# auto_week_3.net
KiCad netlist of a schematic drawn in EAGLE
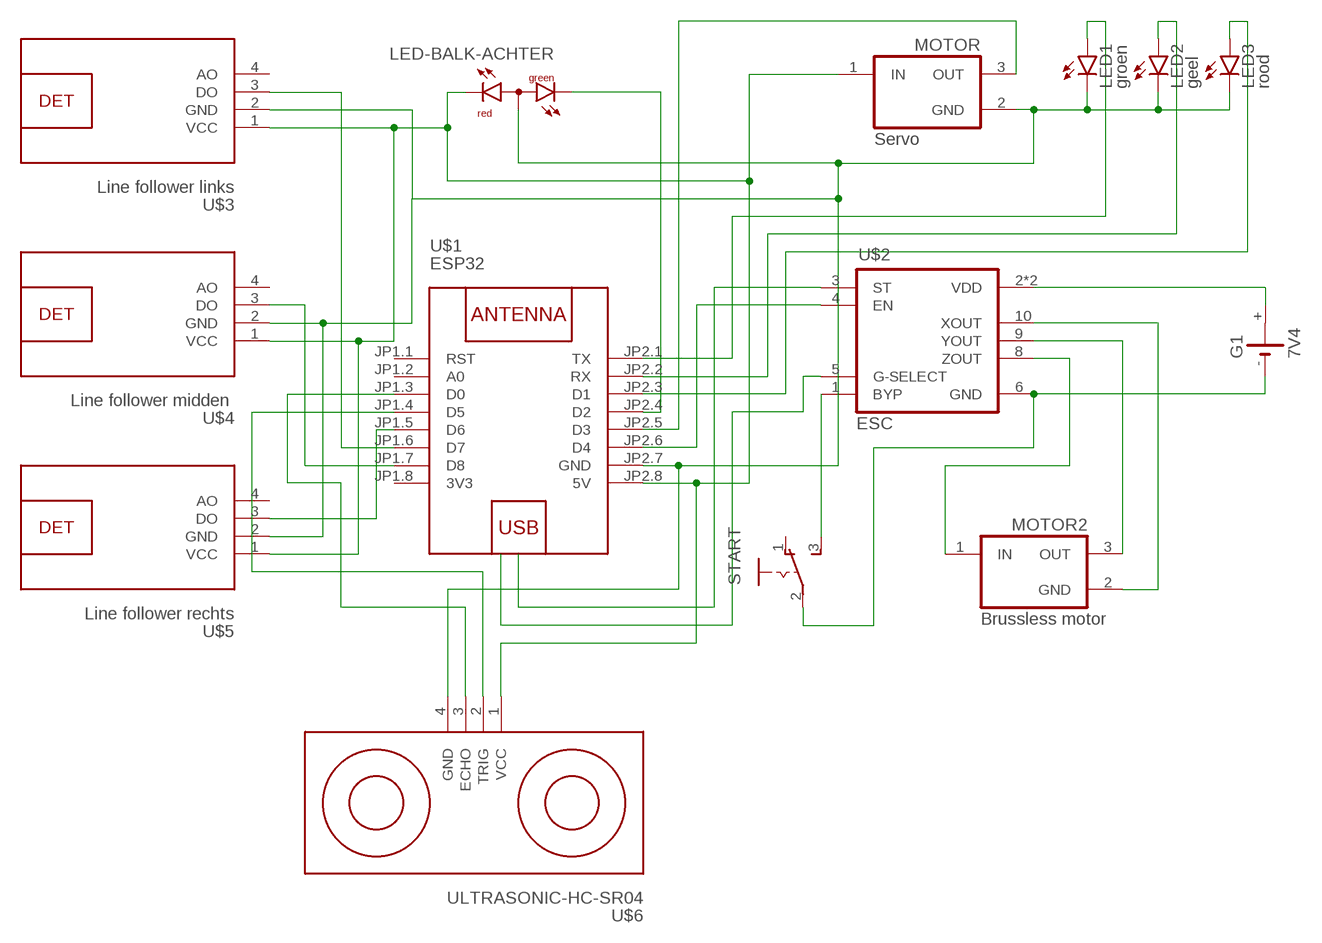
[diagram p0: schematic, sheet 1]

(export (version "E")
  (design (tool "Eeschema 10.0.6"))
  (components
    (comp (ref "G1")
      (value "7V4")
      (footprint "eagle-import:1V60R")
      (libsource (lib "eagle-import") (part "1V60R"))
    )
    (comp (ref "LED-BALK-ACHTER")
      (value "DUOLED-RG-A")
      (footprint "eagle-import:DUOLED-A-5MM")
      (libsource (lib "eagle-import") (part "DUOLED-RG-A"))
    )
    (comp (ref "LED1")
      (value "groen")
      (footprint "eagle-import:P47F-BOTTOM")
      (libsource (lib "eagle-import") (part "P4-BOTTOMLA"))
    )
    (comp (ref "LED2")
      (value "geel")
      (footprint "eagle-import:P47F-BOTTOM")
      (libsource (lib "eagle-import") (part "P4-BOTTOMLA"))
    )
    (comp (ref "LED3")
      (value "rood")
      (footprint "eagle-import:P47F-BOTTOM")
      (libsource (lib "eagle-import") (part "P4-BOTTOMLA"))
    )
    (comp (ref "MOTOR")
      (value "Servo")
      (footprint "eagle-import:TO220-S")
      (libsource (lib "eagle-import") (part "MIC29300-3.3BT"))
    )
    (comp (ref "MOTOR2")
      (value "Brussless motor")
      (footprint "eagle-import:TO220-S")
      (libsource (lib "eagle-import") (part "MIC29300-3.3BT"))
    )
    (comp (ref "START")
      (value "255SB")
      (footprint "eagle-import:255SB")
      (libsource (lib "eagle-import") (part "255SB"))
    )
    (comp (ref "U$1")
      (value "ESP32")
      (footprint "eagle-import:WEMOS-D1-MINI")
      (libsource (lib "eagle-import") (part "WEMOS-D1-MINI"))
    )
    (comp (ref "U$2")
      (value "ESC")
      (footprint "eagle-import:QFN12-3X3")
      (libsource (lib "eagle-import") (part "FXLN83XXQ"))
    )
    (comp (ref "U$3")
      (value "Line follower links")
      (footprint "eagle-import:FLAME-DETECTOR")
      (libsource (lib "eagle-import") (part "FLAME-DETECTOR"))
    )
    (comp (ref "U$4")
      (value "Line follower midden")
      (footprint "eagle-import:FLAME-DETECTOR")
      (libsource (lib "eagle-import") (part "FLAME-DETECTOR"))
    )
    (comp (ref "U$5")
      (value "Line follower rechts")
      (footprint "eagle-import:FLAME-DETECTOR")
      (libsource (lib "eagle-import") (part "FLAME-DETECTOR"))
    )
    (comp (ref "U$6")
      (value "ULTRASONIC-HC-SR04")
      (footprint "eagle-import:ULTRASONIC-HC-SR04")
      (libsource (lib "eagle-import") (part "ULTRASONIC-HC-SR04"))
    )
  )
  (nets
    (net (code "1") (name "/3V3") (class "Default")
      (node (ref "U$1") (pin "JP1.8") (pinfunction "3V3_JP1.8") (pintype "power_in"))
    )
    (net (code "2") (name "Net-(G1-Pad+)") (class "Default")
      (node (ref "G1") (pin "+") (pinfunction "+_+") (pintype "passive"))
      (node (ref "U$2") (pin "2") (pinfunction "VDD_2") (pintype "power_in"))
      (node (ref "U$2") (pin "7") (pinfunction "VDD_7") (pintype "power_in"))
    )
    (net (code "3") (name "Net-(LED-BALK-ACHTER-CG)") (class "Default")
      (node (ref "LED-BALK-ACHTER") (pin "CX") (pinfunction "CG_CX") (pintype "passive"))
      (node (ref "U$1") (pin "JP2.4") (pinfunction "D2_JP2.4") (pintype "bidirectional"))
    )
    (net (code "4") (name "Net-(MOTOR-GND)") (class "Default")
      (node (ref "LED-BALK-ACHTER") (pin "A") (pinfunction "A_A") (pintype "passive"))
      (node (ref "LED1") (pin "C") (pinfunction "C_C") (pintype "passive"))
      (node (ref "LED2") (pin "C") (pinfunction "C_C") (pintype "passive"))
      (node (ref "LED3") (pin "C") (pinfunction "C_C") (pintype "passive"))
      (node (ref "MOTOR") (pin "2") (pinfunction "GND_2") (pintype "power_in"))
      (node (ref "U$1") (pin "JP2.7") (pinfunction "GND_JP2.7") (pintype "power_in"))
      (node (ref "U$3") (pin "2") (pinfunction "GND_2") (pintype "power_in"))
      (node (ref "U$4") (pin "2") (pinfunction "GND_2") (pintype "power_in"))
      (node (ref "U$5") (pin "2") (pinfunction "GND_2") (pintype "power_in"))
      (node (ref "U$6") (pin "4") (pinfunction "GND_4") (pintype "power_in"))
    )
    (net (code "5") (name "Net-(MOTOR-IN)") (class "Default")
      (node (ref "LED-BALK-ACHTER") (pin "CR") (pinfunction "CR_CR") (pintype "passive"))
      (node (ref "MOTOR") (pin "1") (pinfunction "IN_1") (pintype "passive"))
      (node (ref "U$1") (pin "JP2.8") (pinfunction "5V_JP2.8") (pintype "power_in"))
      (node (ref "U$3") (pin "1") (pinfunction "VCC_1") (pintype "power_in"))
      (node (ref "U$4") (pin "1") (pinfunction "VCC_1") (pintype "power_in"))
      (node (ref "U$5") (pin "1") (pinfunction "VCC_1") (pintype "power_in"))
      (node (ref "U$6") (pin "1") (pinfunction "VCC_1") (pintype "power_in"))
    )
    (net (code "6") (name "Net-(MOTOR-OUT)") (class "Default")
      (node (ref "MOTOR") (pin "3") (pinfunction "OUT_3") (pintype "passive"))
      (node (ref "U$1") (pin "JP2.5") (pinfunction "D3_JP2.5") (pintype "bidirectional"))
    )
    (net (code "7") (name "Net-(MOTOR2-GND)") (class "Default")
      (node (ref "MOTOR2") (pin "2") (pinfunction "GND_2") (pintype "power_in"))
      (node (ref "U$2") (pin "10") (pinfunction "XOUT_10") (pintype "output"))
    )
    (net (code "8") (name "Net-(MOTOR2-IN)") (class "Default")
      (node (ref "MOTOR2") (pin "1") (pinfunction "IN_1") (pintype "passive"))
      (node (ref "U$2") (pin "8") (pinfunction "ZOUT_8") (pintype "output"))
    )
    (net (code "9") (name "Net-(MOTOR2-OUT)") (class "Default")
      (node (ref "MOTOR2") (pin "3") (pinfunction "OUT_3") (pintype "passive"))
      (node (ref "U$2") (pin "9") (pinfunction "YOUT_9") (pintype "output"))
    )
    (net (code "10") (name "Net-(START-P)") (class "Default")
      (node (ref "G1") (pin "-") (pinfunction "-_-") (pintype "passive"))
      (node (ref "START") (pin "2") (pinfunction "P_2") (pintype "passive"))
      (node (ref "U$2") (pin "6") (pinfunction "GND_6") (pintype "power_in"))
    )
    (net (code "11") (name "Net-(START-S)") (class "Default")
      (node (ref "START") (pin "3") (pinfunction "S_3") (pintype "passive"))
      (node (ref "U$2") (pin "1") (pinfunction "BYP_1") (pintype "bidirectional"))
    )
    (net (code "12") (name "Net-(U$1-D0)") (class "Default")
      (node (ref "U$1") (pin "JP1.3") (pinfunction "D0_JP1.3") (pintype "bidirectional"))
      (node (ref "U$6") (pin "3") (pinfunction "ECHO_3") (pintype "output"))
    )
    (net (code "13") (name "Net-(U$1-D1)") (class "Default")
      (node (ref "LED3") (pin "A") (pinfunction "A_A") (pintype "passive"))
      (node (ref "U$1") (pin "JP2.3") (pinfunction "D1_JP2.3") (pintype "bidirectional"))
    )
    (net (code "14") (name "Net-(U$1-D4)") (class "Default")
      (node (ref "U$1") (pin "JP2.6") (pinfunction "D4_JP2.6") (pintype "bidirectional"))
      (node (ref "U$2") (pin "4") (pinfunction "EN_4") (pintype "bidirectional"))
    )
    (net (code "15") (name "Net-(U$1-D5)") (class "Default")
      (node (ref "U$1") (pin "JP1.4") (pinfunction "D5_JP1.4") (pintype "bidirectional"))
      (node (ref "U$6") (pin "2") (pinfunction "TRIG_2") (pintype "input"))
    )
    (net (code "16") (name "Net-(U$1-D6)") (class "Default")
      (node (ref "U$1") (pin "JP1.5") (pinfunction "D6_JP1.5") (pintype "bidirectional"))
      (node (ref "U$5") (pin "3") (pinfunction "DO_3") (pintype "bidirectional"))
    )
    (net (code "17") (name "Net-(U$1-D7)") (class "Default")
      (node (ref "U$1") (pin "JP1.6") (pinfunction "D7_JP1.6") (pintype "bidirectional"))
      (node (ref "U$3") (pin "3") (pinfunction "DO_3") (pintype "bidirectional"))
    )
    (net (code "18") (name "Net-(U$1-D8)") (class "Default")
      (node (ref "U$1") (pin "JP1.7") (pinfunction "D8_JP1.7") (pintype "bidirectional"))
      (node (ref "U$4") (pin "3") (pinfunction "DO_3") (pintype "bidirectional"))
    )
    (net (code "19") (name "Net-(U$1-RX)") (class "Default")
      (node (ref "LED2") (pin "A") (pinfunction "A_A") (pintype "passive"))
      (node (ref "U$1") (pin "JP2.2") (pinfunction "RX_JP2.2") (pintype "bidirectional"))
    )
    (net (code "20") (name "Net-(U$1-TX)") (class "Default")
      (node (ref "LED1") (pin "A") (pinfunction "A_A") (pintype "passive"))
      (node (ref "U$1") (pin "JP2.1") (pinfunction "TX_JP2.1") (pintype "bidirectional"))
    )
    (net (code "21") (name "unconnected-(G1-+-Pad+@1)") (class "Default")
      (node (ref "G1") (pin "+@1") (pinfunction "+_+@1") (pintype "passive"))
    )
    (net (code "22") (name "unconnected-(START-O-Pad1)") (class "Default")
      (node (ref "START") (pin "1") (pinfunction "O_1") (pintype "passive"))
    )
    (net (code "23") (name "unconnected-(U$1-A0-PadJP1.2)") (class "Default")
      (node (ref "U$1") (pin "JP1.2") (pinfunction "A0_JP1.2") (pintype "bidirectional"))
    )
    (net (code "24") (name "unconnected-(U$1-RST-PadJP1.1)") (class "Default")
      (node (ref "U$1") (pin "JP1.1") (pinfunction "RST_JP1.1") (pintype "bidirectional"))
    )
    (net (code "25") (name "unconnected-(U$2-G-SELECT-Pad5)") (class "Default")
      (node (ref "U$2") (pin "5") (pinfunction "G-SELECT_5") (pintype "bidirectional"))
    )
    (net (code "26") (name "unconnected-(U$2-ST-Pad3)") (class "Default")
      (node (ref "U$2") (pin "3") (pinfunction "ST_3") (pintype "bidirectional"))
    )
    (net (code "27") (name "unconnected-(U$3-AO-Pad4)") (class "Default")
      (node (ref "U$3") (pin "4") (pinfunction "AO_4") (pintype "bidirectional"))
    )
    (net (code "28") (name "unconnected-(U$4-AO-Pad4)") (class "Default")
      (node (ref "U$4") (pin "4") (pinfunction "AO_4") (pintype "bidirectional"))
    )
    (net (code "29") (name "unconnected-(U$5-AO-Pad4)") (class "Default")
      (node (ref "U$5") (pin "4") (pinfunction "AO_4") (pintype "bidirectional"))
    )
  )
)
